# LV_Relay_Board_v6.net
KiCad netlist of a schematic drawn in EAGLE
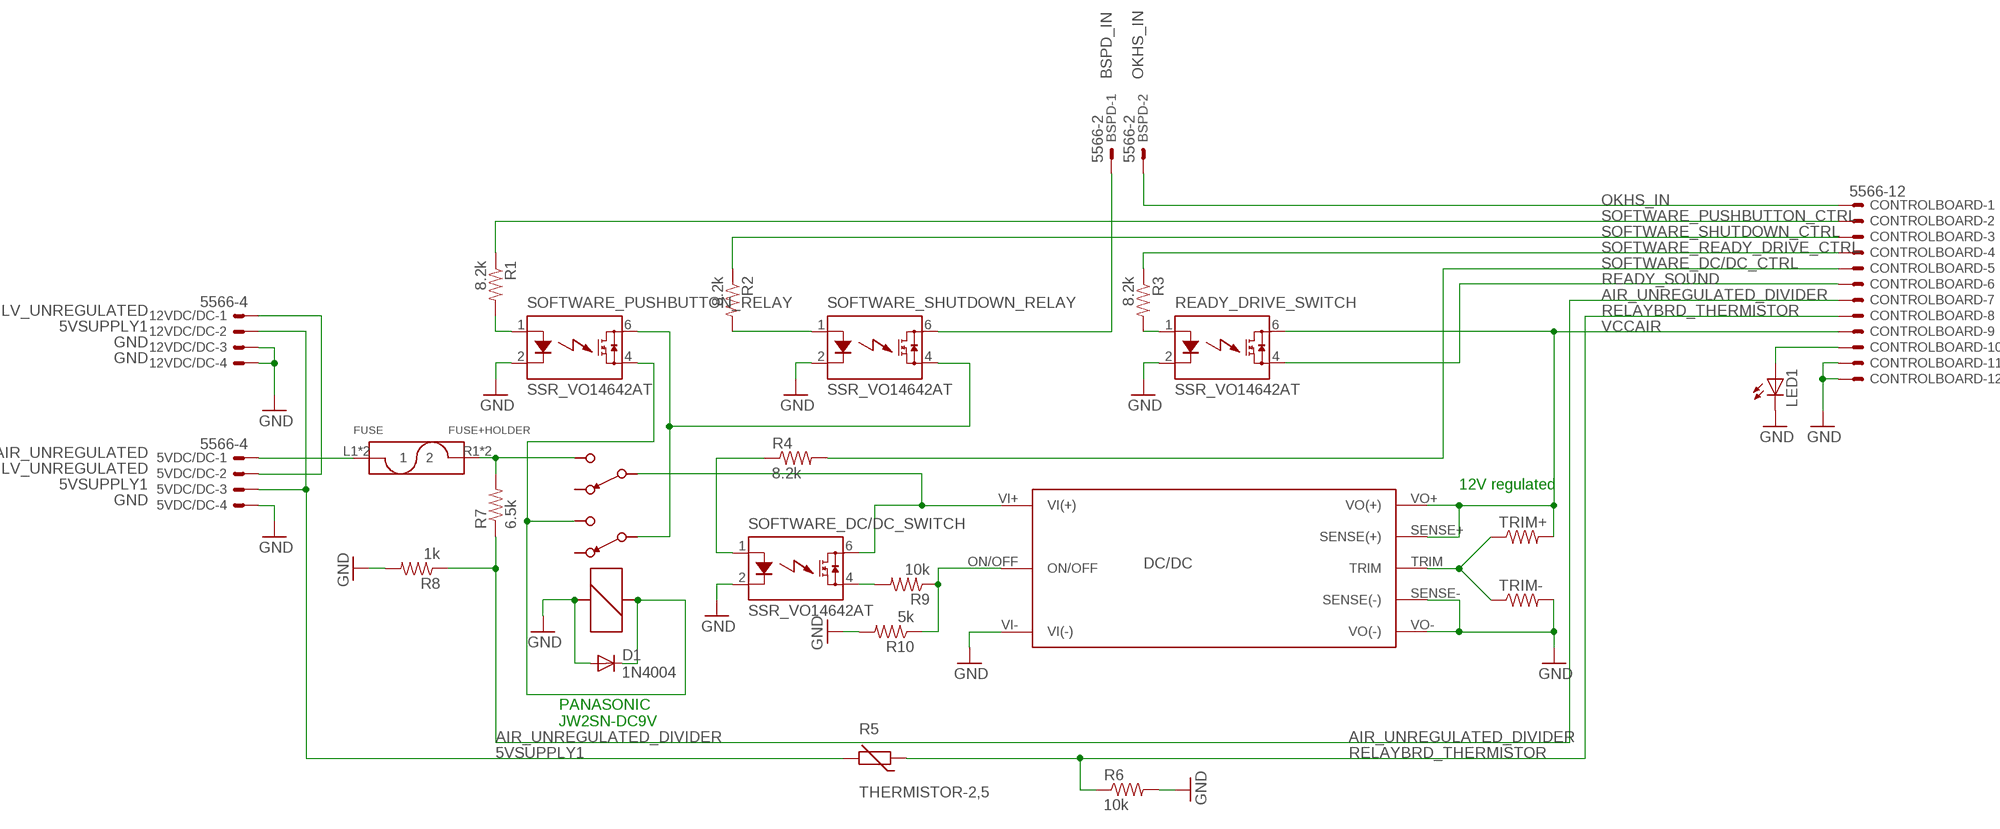
[diagram p0: schematic, sheet 1]

(export (version "E")
  (design (tool "Eeschema 10.0.6"))
  (components
    (comp (ref "5VDC/DC")
      (value "5566-4")
      (footprint "eagle-import:5566-4")
      (libsource (lib "eagle-import") (part "5566-4"))
    )
    (comp (ref "12VDC/DC")
      (value "5566-4")
      (footprint "eagle-import:5566-4")
      (libsource (lib "eagle-import") (part "5566-4"))
    )
    (comp (ref "BSPD")
      (value "5566-2")
      (footprint "eagle-import:5566-2")
      (libsource (lib "eagle-import") (part "5566-2"))
    )
    (comp (ref "CONTROLBOARD")
      (value "5566-12")
      (footprint "eagle-import:5566-12")
      (libsource (lib "eagle-import") (part "5566-12"))
    )
    (comp (ref "D1")
      (value "1N4004")
      (footprint "eagle-import:DO41-10")
      (libsource (lib "eagle-import") (part "1N4004"))
    )
    (comp (ref "DC/DC")
      (value "DC/DC-EIGHTH_BRICKUWE-12/10-Q12PB-C")
      (footprint "eagle-import:DC_DC-EIGHTH_BRICK")
      (libsource (lib "eagle-import") (part "DC/DC-EIGHTH_BRICKUWE-12/10-Q12PB-C"))
    )
    (comp (ref "FUSE")
      (value "FUSE+HOLDER")
      (footprint "eagle-import:FUSE-HOLDER")
      (libsource (lib "eagle-import") (part "FUSE+HOLDER"))
    )
    (comp (ref "LED1")
      (value "LED3MM")
      (footprint "eagle-import:LED3MM")
      (libsource (lib "eagle-import") (part "LED3MM"))
    )
    (comp (ref "PANASONIC_JW2SN-DC9V_RELAY")
      (value "PANASONIC_JW2SN-DC9V_RELAY")
      (footprint "eagle-import:PANASONIC_JW2SN-DC9V_RELAY")
      (libsource (lib "eagle-import") (part "PANASONIC_JW2SN-DC9V_RELAY"))
    )
    (comp (ref "R1")
      (value "8.2k")
      (footprint "eagle-import:AXIAL-0.4")
      (libsource (lib "eagle-import") (part "RESISTORPTH-1/4W"))
    )
    (comp (ref "R2")
      (value "8.2k")
      (footprint "eagle-import:AXIAL-0.4")
      (libsource (lib "eagle-import") (part "RESISTORPTH-1/4W"))
    )
    (comp (ref "R3")
      (value "8.2k")
      (footprint "eagle-import:AXIAL-0.4")
      (libsource (lib "eagle-import") (part "RESISTORPTH-1/4W"))
    )
    (comp (ref "R4")
      (value "8.2k")
      (footprint "eagle-import:AXIAL-0.4")
      (libsource (lib "eagle-import") (part "RESISTORPTH-1/4W"))
    )
    (comp (ref "R5")
      (value "THERMISTOR-2,5")
      (footprint "eagle-import:RS-2,5")
      (libsource (lib "eagle-import") (part "THERMISTOR-2,5"))
    )
    (comp (ref "R6")
      (value "10k")
      (footprint "eagle-import:AXIAL-0.4")
      (libsource (lib "eagle-import") (part "RESISTORPTH-1/4W"))
    )
    (comp (ref "R7")
      (value "6.5k")
      (footprint "eagle-import:AXIAL-0.4")
      (libsource (lib "eagle-import") (part "RESISTORPTH-1/4W"))
    )
    (comp (ref "R8")
      (value "1k")
      (footprint "eagle-import:AXIAL-0.4")
      (libsource (lib "eagle-import") (part "RESISTORPTH-1/4W"))
    )
    (comp (ref "R9")
      (value "10k")
      (footprint "eagle-import:AXIAL-0.4")
      (libsource (lib "eagle-import") (part "RESISTORPTH-1/4W"))
    )
    (comp (ref "R10")
      (value "5k")
      (footprint "eagle-import:AXIAL-0.4")
      (libsource (lib "eagle-import") (part "RESISTORPTH-1/4W"))
    )
    (comp (ref "READY_DRIVE_SWITCH")
      (value "SSR_VO14642AT")
      (footprint "eagle-import:DIL06")
      (libsource (lib "eagle-import") (part "SSR_VO14642AT"))
    )
    (comp (ref "SOFTWARE_DC/DC_SWITCH")
      (value "SSR_VO14642AT")
      (footprint "eagle-import:DIL06")
      (libsource (lib "eagle-import") (part "SSR_VO14642AT"))
    )
    (comp (ref "SOFTWARE_PUSHBUTTON_RELAY")
      (value "SSR_VO14642AT")
      (footprint "eagle-import:DIL06")
      (libsource (lib "eagle-import") (part "SSR_VO14642AT"))
    )
    (comp (ref "SOFTWARE_SHUTDOWN_RELAY")
      (value "SSR_VO14642AT")
      (footprint "eagle-import:DIL06")
      (libsource (lib "eagle-import") (part "SSR_VO14642AT"))
    )
    (comp (ref "TRIM+")
      (value "RESISTORPTH-1/4W")
      (footprint "eagle-import:AXIAL-0.4")
      (libsource (lib "eagle-import") (part "RESISTORPTH-1/4W"))
    )
    (comp (ref "TRIM-")
      (value "RESISTORPTH-1/4W")
      (footprint "eagle-import:AXIAL-0.4")
      (libsource (lib "eagle-import") (part "RESISTORPTH-1/4W"))
    )
  )
  (nets
    (net (code "1") (name "/5VSUPPLY1") (class "Default")
      (node (ref "12VDC/DC") (pin "2") (pinfunction "S_2") (pintype "passive"))
      (node (ref "5VDC/DC") (pin "3") (pinfunction "S_3") (pintype "passive"))
      (node (ref "R5") (pin "2") (pinfunction "2_2") (pintype "passive"))
    )
    (net (code "2") (name "/AIR_UNREGULATED") (class "Default")
      (node (ref "5VDC/DC") (pin "1") (pinfunction "S_1") (pintype "passive"))
      (node (ref "FUSE") (pin "L1") (pinfunction "1_L1") (pintype "bidirectional"))
      (node (ref "FUSE") (pin "L2") (pinfunction "1_L2") (pintype "bidirectional"))
    )
    (net (code "3") (name "/AIR_UNREGULATED_DIVIDER") (class "Default")
      (node (ref "CONTROLBOARD") (pin "7") (pinfunction "S_7") (pintype "passive"))
      (node (ref "R7") (pin "P$1") (pinfunction "1_P$1") (pintype "passive"))
      (node (ref "R8") (pin "P$1") (pinfunction "1_P$1") (pintype "passive"))
    )
    (net (code "4") (name "/BSPD_IN") (class "Default")
      (node (ref "BSPD") (pin "1") (pinfunction "S_1") (pintype "passive"))
      (node (ref "SOFTWARE_SHUTDOWN_RELAY") (pin "6") (pinfunction "IO1_6") (pintype "passive"))
    )
    (net (code "5") (name "/LV_UNREGULATED") (class "Default")
      (node (ref "12VDC/DC") (pin "1") (pinfunction "S_1") (pintype "passive"))
      (node (ref "5VDC/DC") (pin "2") (pinfunction "S_2") (pintype "passive"))
    )
    (net (code "6") (name "/OKHS_IN") (class "Default")
      (node (ref "BSPD") (pin "2") (pinfunction "S_2") (pintype "passive"))
      (node (ref "CONTROLBOARD") (pin "1") (pinfunction "S_1") (pintype "passive"))
    )
    (net (code "7") (name "/READY_SOUND") (class "Default")
      (node (ref "CONTROLBOARD") (pin "6") (pinfunction "S_6") (pintype "passive"))
      (node (ref "READY_DRIVE_SWITCH") (pin "4") (pinfunction "IO2_4") (pintype "passive"))
    )
    (net (code "8") (name "/RELAYBRD_THERMISTOR") (class "Default")
      (node (ref "CONTROLBOARD") (pin "8") (pinfunction "S_8") (pintype "passive"))
      (node (ref "R5") (pin "1") (pinfunction "1_1") (pintype "passive"))
      (node (ref "R6") (pin "P$1") (pinfunction "1_P$1") (pintype "passive"))
    )
    (net (code "9") (name "/SOFTWARE_DC{slash}DC_CTRL") (class "Default")
      (node (ref "CONTROLBOARD") (pin "5") (pinfunction "S_5") (pintype "passive"))
      (node (ref "R4") (pin "P$2") (pinfunction "2_P$2") (pintype "passive"))
    )
    (net (code "10") (name "/SOFTWARE_PUSHBUTTON_CTRL") (class "Default")
      (node (ref "CONTROLBOARD") (pin "2") (pinfunction "S_2") (pintype "passive"))
      (node (ref "R1") (pin "P$1") (pinfunction "1_P$1") (pintype "passive"))
    )
    (net (code "11") (name "/SOFTWARE_READY_DRIVE_CTRL") (class "Default")
      (node (ref "CONTROLBOARD") (pin "4") (pinfunction "S_4") (pintype "passive"))
      (node (ref "R3") (pin "P$1") (pinfunction "1_P$1") (pintype "passive"))
    )
    (net (code "12") (name "/SOFTWARE_SHUTDOWN_CTRL") (class "Default")
      (node (ref "CONTROLBOARD") (pin "3") (pinfunction "S_3") (pintype "passive"))
      (node (ref "R2") (pin "P$1") (pinfunction "1_P$1") (pintype "passive"))
    )
    (net (code "13") (name "/VCCAIR") (class "Default")
      (node (ref "CONTROLBOARD") (pin "9") (pinfunction "S_9") (pintype "passive"))
      (node (ref "DC/DC") (pin "SENSE+") (pinfunction "SENSE(+)_SENSE+") (pintype "bidirectional"))
      (node (ref "DC/DC") (pin "VO+") (pinfunction "VO(+)_VO+") (pintype "bidirectional"))
      (node (ref "READY_DRIVE_SWITCH") (pin "6") (pinfunction "IO1_6") (pintype "passive"))
      (node (ref "TRIM+") (pin "P$2") (pinfunction "2_P$2") (pintype "passive"))
    )
    (net (code "14") (name "GND") (class "Default")
      (node (ref "12VDC/DC") (pin "3") (pinfunction "S_3") (pintype "passive"))
      (node (ref "12VDC/DC") (pin "4") (pinfunction "S_4") (pintype "passive"))
      (node (ref "5VDC/DC") (pin "4") (pinfunction "S_4") (pintype "passive"))
      (node (ref "CONTROLBOARD") (pin "11") (pinfunction "S_11") (pintype "passive"))
      (node (ref "CONTROLBOARD") (pin "12") (pinfunction "S_12") (pintype "passive"))
      (node (ref "D1") (pin "A") (pinfunction "A_A") (pintype "passive"))
      (node (ref "DC/DC") (pin "SENSE-") (pinfunction "SENSE(-)_SENSE-") (pintype "bidirectional"))
      (node (ref "DC/DC") (pin "VI-") (pinfunction "VI(-)_VI-") (pintype "bidirectional"))
      (node (ref "DC/DC") (pin "VO-") (pinfunction "VO(-)_VO-") (pintype "bidirectional"))
      (node (ref "LED1") (pin "K") (pinfunction "C_K") (pintype "passive"))
      (node (ref "PANASONIC_JW2SN-DC9V_RELAY") (pin "COIL+") (pinfunction "COIL+_COIL+") (pintype "bidirectional"))
      (node (ref "R10") (pin "P$2") (pinfunction "2_P$2") (pintype "passive"))
      (node (ref "R6") (pin "P$2") (pinfunction "2_P$2") (pintype "passive"))
      (node (ref "R8") (pin "P$2") (pinfunction "2_P$2") (pintype "passive"))
      (node (ref "READY_DRIVE_SWITCH") (pin "2") (pinfunction "LED-_2") (pintype "passive"))
      (node (ref "SOFTWARE_DC/DC_SWITCH") (pin "2") (pinfunction "LED-_2") (pintype "passive"))
      (node (ref "SOFTWARE_PUSHBUTTON_RELAY") (pin "2") (pinfunction "LED-_2") (pintype "passive"))
      (node (ref "SOFTWARE_SHUTDOWN_RELAY") (pin "2") (pinfunction "LED-_2") (pintype "passive"))
      (node (ref "TRIM-") (pin "P$2") (pinfunction "2_P$2") (pintype "passive"))
    )
    (net (code "15") (name "Net-(CONTROLBOARDB-S)") (class "Default")
      (node (ref "CONTROLBOARD") (pin "10") (pinfunction "S_10") (pintype "passive"))
      (node (ref "LED1") (pin "A") (pinfunction "A_A") (pintype "passive"))
    )
    (net (code "16") (name "Net-(DC/DC-VI(+))") (class "Default")
      (node (ref "DC/DC") (pin "VI+") (pinfunction "VI(+)_VI+") (pintype "bidirectional"))
      (node (ref "PANASONIC_JW2SN-DC9V_RELAY") (pin "6") (pinfunction "6_6") (pintype "bidirectional"))
      (node (ref "SOFTWARE_DC/DC_SWITCH") (pin "6") (pinfunction "IO1_6") (pintype "passive"))
    )
    (net (code "17") (name "Net-(R1-2)") (class "Default")
      (node (ref "R1") (pin "P$2") (pinfunction "2_P$2") (pintype "passive"))
      (node (ref "SOFTWARE_PUSHBUTTON_RELAY") (pin "1") (pinfunction "LED+_1") (pintype "passive"))
    )
    (net (code "18") (name "Net-(R2-2)") (class "Default")
      (node (ref "R2") (pin "P$2") (pinfunction "2_P$2") (pintype "passive"))
      (node (ref "SOFTWARE_SHUTDOWN_RELAY") (pin "1") (pinfunction "LED+_1") (pintype "passive"))
    )
    (net (code "19") (name "Net-(R3-2)") (class "Default")
      (node (ref "R3") (pin "P$2") (pinfunction "2_P$2") (pintype "passive"))
      (node (ref "READY_DRIVE_SWITCH") (pin "1") (pinfunction "LED+_1") (pintype "passive"))
    )
    (net (code "20") (name "Net-(R4-1)") (class "Default")
      (node (ref "R4") (pin "P$1") (pinfunction "1_P$1") (pintype "passive"))
      (node (ref "SOFTWARE_DC/DC_SWITCH") (pin "1") (pinfunction "LED+_1") (pintype "passive"))
    )
    (net (code "21") (name "Net-(R7-2)") (class "Default")
      (node (ref "FUSE") (pin "R1") (pinfunction "2_R1") (pintype "bidirectional"))
      (node (ref "FUSE") (pin "R2") (pinfunction "2_R2") (pintype "bidirectional"))
      (node (ref "PANASONIC_JW2SN-DC9V_RELAY") (pin "5") (pinfunction "5_5") (pintype "bidirectional"))
      (node (ref "R7") (pin "P$2") (pinfunction "2_P$2") (pintype "passive"))
    )
    (net (code "22") (name "Net-(R9-2)") (class "Default")
      (node (ref "R9") (pin "P$2") (pinfunction "2_P$2") (pintype "passive"))
      (node (ref "SOFTWARE_DC/DC_SWITCH") (pin "4") (pinfunction "IO2_4") (pintype "passive"))
    )
    (net (code "23") (name "Net-(R10-1)") (class "Default")
      (node (ref "DC/DC") (pin "ON/OFF") (pinfunction "ON/OFF_ON/OFF") (pintype "bidirectional"))
      (node (ref "R10") (pin "P$1") (pinfunction "1_P$1") (pintype "passive"))
      (node (ref "R9") (pin "P$1") (pinfunction "1_P$1") (pintype "passive"))
    )
    (net (code "24") (name "Net-(SOFTWARE_PUSHBUTTON_RELAY-IO1)") (class "Default")
      (node (ref "PANASONIC_JW2SN-DC9V_RELAY") (pin "3") (pinfunction "3_3") (pintype "bidirectional"))
      (node (ref "SOFTWARE_PUSHBUTTON_RELAY") (pin "6") (pinfunction "IO1_6") (pintype "passive"))
      (node (ref "SOFTWARE_SHUTDOWN_RELAY") (pin "4") (pinfunction "IO2_4") (pintype "passive"))
    )
    (net (code "25") (name "Net-(SOFTWARE_PUSHBUTTON_RELAY-IO2)") (class "Default")
      (node (ref "D1") (pin "C") (pinfunction "C_C") (pintype "passive"))
      (node (ref "PANASONIC_JW2SN-DC9V_RELAY") (pin "4") (pinfunction "4_4") (pintype "bidirectional"))
      (node (ref "PANASONIC_JW2SN-DC9V_RELAY") (pin "COIL-") (pinfunction "COIL-_COIL-") (pintype "bidirectional"))
      (node (ref "SOFTWARE_PUSHBUTTON_RELAY") (pin "4") (pinfunction "IO2_4") (pintype "passive"))
    )
    (net (code "26") (name "Net-(TRIM+-1)") (class "Default")
      (node (ref "DC/DC") (pin "TRIM") (pinfunction "TRIM_TRIM") (pintype "bidirectional"))
      (node (ref "TRIM+") (pin "P$1") (pinfunction "1_P$1") (pintype "passive"))
      (node (ref "TRIM-") (pin "P$1") (pinfunction "1_P$1") (pintype "passive"))
    )
    (net (code "27") (name "unconnected-(PANASONIC_JW2SN-DC9V_RELAY-Pad2)") (class "Default")
      (node (ref "PANASONIC_JW2SN-DC9V_RELAY") (pin "2") (pinfunction "2_2") (pintype "bidirectional"))
    )
    (net (code "28") (name "unconnected-(PANASONIC_JW2SN-DC9V_RELAY-Pad7)") (class "Default")
      (node (ref "PANASONIC_JW2SN-DC9V_RELAY") (pin "7") (pinfunction "7_7") (pintype "bidirectional"))
    )
  )
)
